# yabr6v3.net
KiCad netlist of a schematic drawn in EAGLE
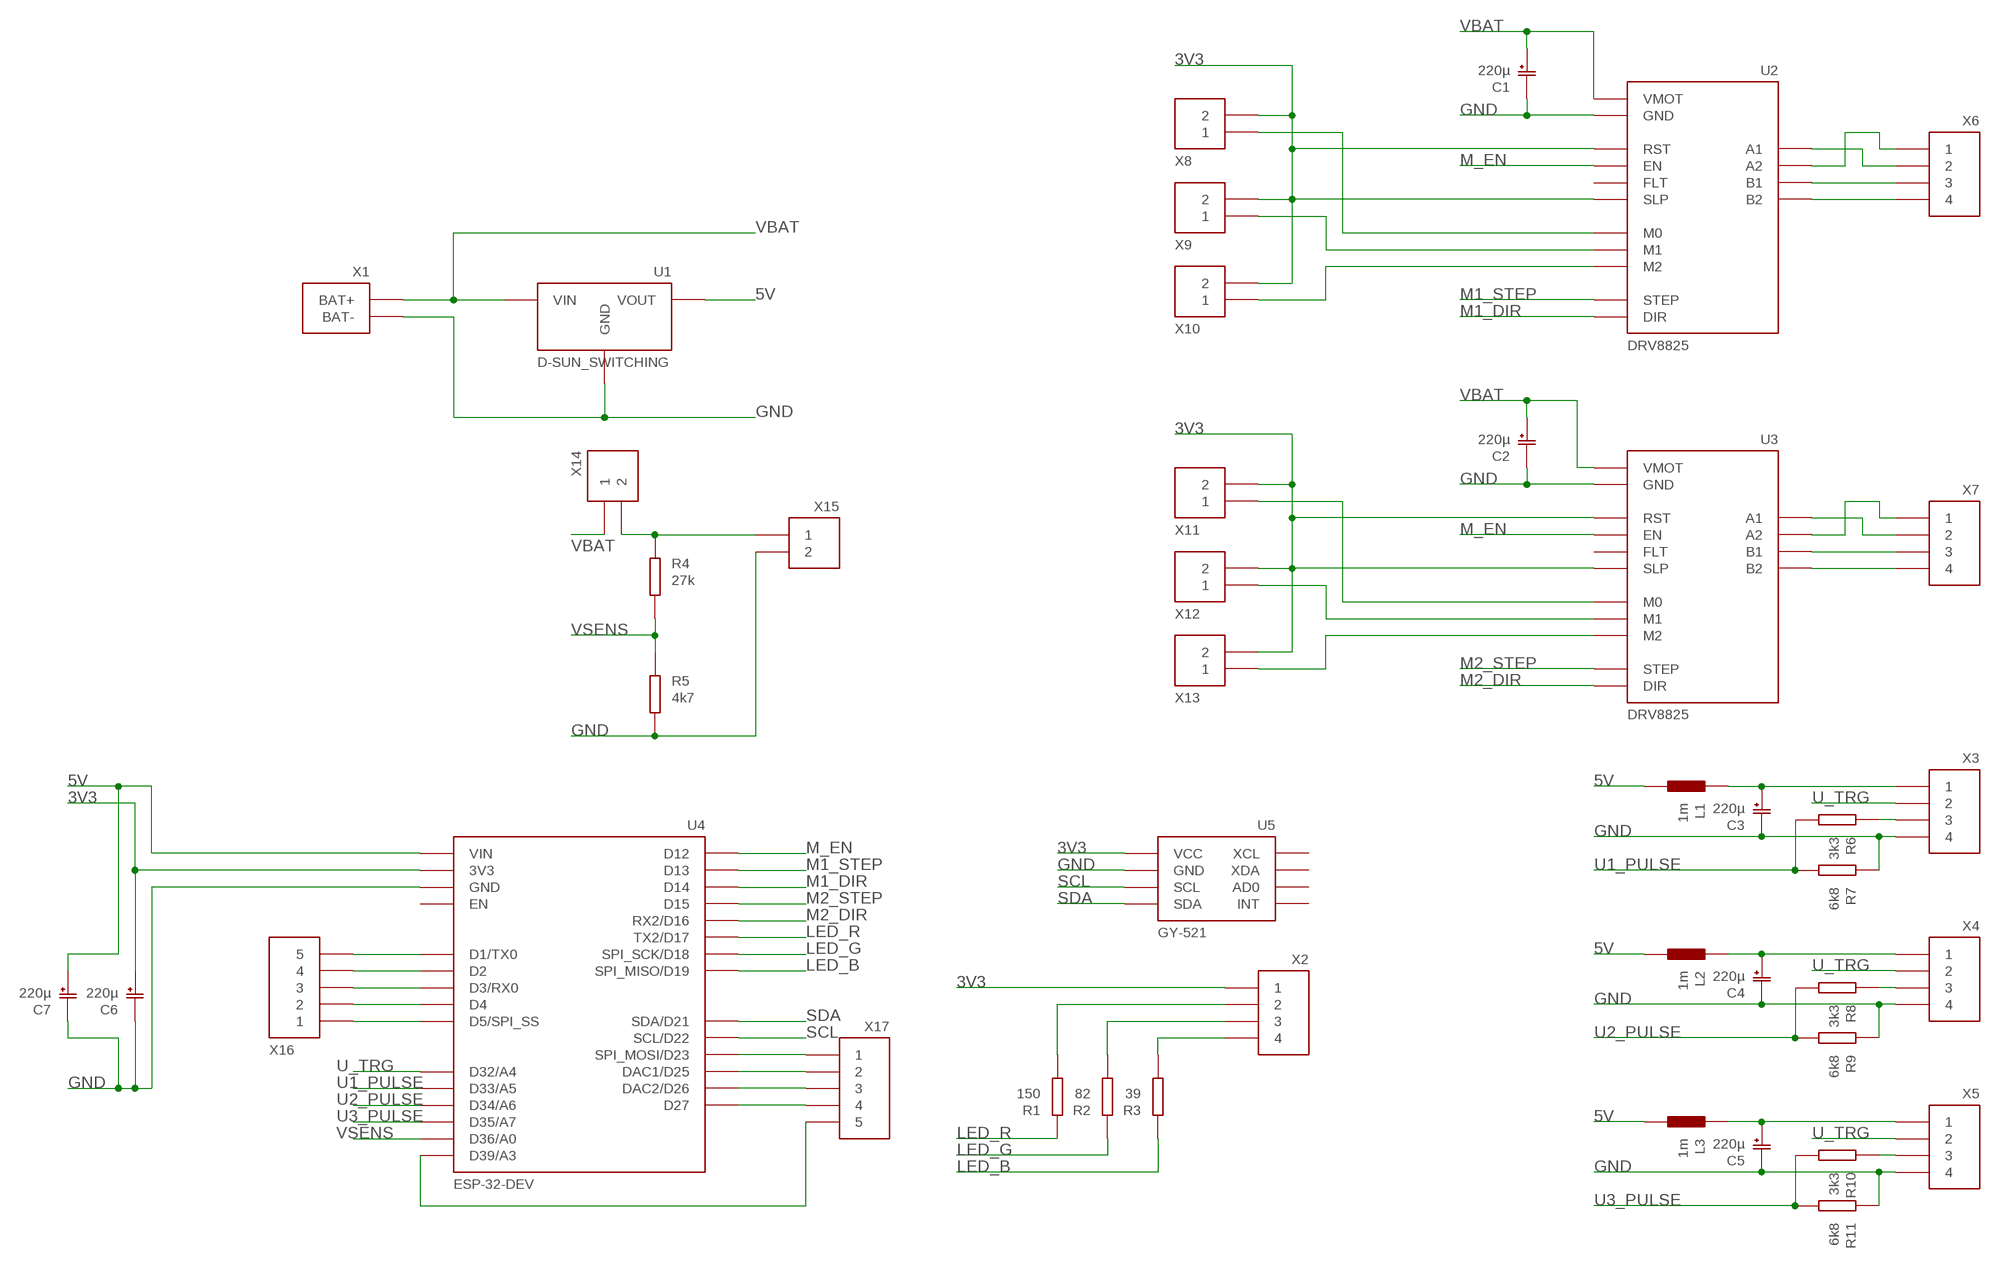
[diagram p0: schematic, sheet 1]

(export (version "E")
  (design (tool "Eeschema 10.0.6"))
  (components
    (comp (ref "C1")
      (value "220µ")
      (footprint "eagle-import:CPOL_3,5")
      (libsource (lib "eagle-import") (part "CPOL3,5"))
    )
    (comp (ref "C2")
      (value "220µ")
      (footprint "eagle-import:CPOL_3,5")
      (libsource (lib "eagle-import") (part "CPOL3,5"))
    )
    (comp (ref "C3")
      (value "220µ")
      (footprint "eagle-import:CPOL_3,5")
      (libsource (lib "eagle-import") (part "CPOL3,5"))
    )
    (comp (ref "C4")
      (value "220µ")
      (footprint "eagle-import:CPOL_3,5")
      (libsource (lib "eagle-import") (part "CPOL3,5"))
    )
    (comp (ref "C5")
      (value "220µ")
      (footprint "eagle-import:CPOL_3,5")
      (libsource (lib "eagle-import") (part "CPOL3,5"))
    )
    (comp (ref "C6")
      (value "220µ")
      (footprint "eagle-import:CPOL_3,5")
      (libsource (lib "eagle-import") (part "CPOL3,5"))
    )
    (comp (ref "C7")
      (value "220µ")
      (footprint "eagle-import:CPOL_3,5")
      (libsource (lib "eagle-import") (part "CPOL3,5"))
    )
    (comp (ref "L1")
      (value "1m")
      (footprint "eagle-import:NEOSID_SD75")
      (libsource (lib "eagle-import") (part "L_NEO"))
    )
    (comp (ref "L2")
      (value "1m")
      (footprint "eagle-import:NEOSID_SD75")
      (libsource (lib "eagle-import") (part "L_NEO"))
    )
    (comp (ref "L3")
      (value "1m")
      (footprint "eagle-import:NEOSID_SD75")
      (libsource (lib "eagle-import") (part "L_NEO"))
    )
    (comp (ref "R1")
      (value "150")
      (footprint "eagle-import:R_12")
      (libsource (lib "eagle-import") (part "R12"))
    )
    (comp (ref "R2")
      (value "82")
      (footprint "eagle-import:R_12")
      (libsource (lib "eagle-import") (part "R12"))
    )
    (comp (ref "R3")
      (value "39")
      (footprint "eagle-import:R_12")
      (libsource (lib "eagle-import") (part "R12"))
    )
    (comp (ref "R4")
      (value "27k")
      (footprint "eagle-import:R_12")
      (libsource (lib "eagle-import") (part "R12"))
    )
    (comp (ref "R5")
      (value "4k7")
      (footprint "eagle-import:R_12")
      (libsource (lib "eagle-import") (part "R12"))
    )
    (comp (ref "R6")
      (value "3k3")
      (footprint "eagle-import:R_12")
      (libsource (lib "eagle-import") (part "R12"))
    )
    (comp (ref "R7")
      (value "6k8")
      (footprint "eagle-import:R_12")
      (libsource (lib "eagle-import") (part "R12"))
    )
    (comp (ref "R8")
      (value "3k3")
      (footprint "eagle-import:R_12")
      (libsource (lib "eagle-import") (part "R12"))
    )
    (comp (ref "R9")
      (value "6k8")
      (footprint "eagle-import:R_12")
      (libsource (lib "eagle-import") (part "R12"))
    )
    (comp (ref "R10")
      (value "3k3")
      (footprint "eagle-import:R_12")
      (libsource (lib "eagle-import") (part "R12"))
    )
    (comp (ref "R11")
      (value "6k8")
      (footprint "eagle-import:R_12")
      (libsource (lib "eagle-import") (part "R12"))
    )
    (comp (ref "U1")
      (value "D-SUN_SWITCHING")
      (footprint "eagle-import:D-SUN_SWITCHING")
      (libsource (lib "eagle-import") (part "D-SUN_SWITCHING"))
    )
    (comp (ref "U2")
      (value "DRV8825")
      (footprint "eagle-import:DRV8825")
      (libsource (lib "eagle-import") (part "DRV8825"))
    )
    (comp (ref "U3")
      (value "DRV8825")
      (footprint "eagle-import:DRV8825")
      (libsource (lib "eagle-import") (part "DRV8825"))
    )
    (comp (ref "U4")
      (value "ESP-32-DEV")
      (footprint "eagle-import:ESP-32-DEV")
      (libsource (lib "eagle-import") (part "ESP-32-DEV"))
    )
    (comp (ref "U5")
      (value "GY-521")
      (footprint "eagle-import:GY-521")
      (libsource (lib "eagle-import") (part "GY-521"))
    )
    (comp (ref "X1")
      (value "BAT")
      (footprint "eagle-import:BAT")
      (libsource (lib "eagle-import") (part "BAT"))
    )
    (comp (ref "X2") (value "X4") (footprint "eagle-import:X4") (libsource (lib "eagle-import") (part "X4")))
    (comp (ref "X3") (value "X4") (footprint "eagle-import:X4") (libsource (lib "eagle-import") (part "X4")))
    (comp (ref "X4") (value "X4") (footprint "eagle-import:X4") (libsource (lib "eagle-import") (part "X4")))
    (comp (ref "X5") (value "X4") (footprint "eagle-import:X4") (libsource (lib "eagle-import") (part "X4")))
    (comp (ref "X6") (value "X4") (footprint "eagle-import:X4") (libsource (lib "eagle-import") (part "X4")))
    (comp (ref "X7") (value "X4") (footprint "eagle-import:X4") (libsource (lib "eagle-import") (part "X4")))
    (comp (ref "X8") (value "X2") (footprint "eagle-import:X2") (libsource (lib "eagle-import") (part "X2")))
    (comp (ref "X9") (value "X2") (footprint "eagle-import:X2") (libsource (lib "eagle-import") (part "X2")))
    (comp (ref "X10") (value "X2") (footprint "eagle-import:X2") (libsource (lib "eagle-import") (part "X2")))
    (comp (ref "X11") (value "X2") (footprint "eagle-import:X2") (libsource (lib "eagle-import") (part "X2")))
    (comp (ref "X12") (value "X2") (footprint "eagle-import:X2") (libsource (lib "eagle-import") (part "X2")))
    (comp (ref "X13") (value "X2") (footprint "eagle-import:X2") (libsource (lib "eagle-import") (part "X2")))
    (comp (ref "X14") (value "X2") (footprint "eagle-import:X2") (libsource (lib "eagle-import") (part "X2")))
    (comp (ref "X15") (value "X2") (footprint "eagle-import:X2") (libsource (lib "eagle-import") (part "X2")))
    (comp (ref "X16") (value "X5") (footprint "eagle-import:X5") (libsource (lib "eagle-import") (part "X5")))
    (comp (ref "X17") (value "X5") (footprint "eagle-import:X5") (libsource (lib "eagle-import") (part "X5")))
  )
  (nets
    (net (code "1") (name "/3V3") (class "Default")
      (node (ref "C6") (pin "P") (pinfunction "+_P") (pintype "bidirectional"))
      (node (ref "U2") (pin "P$11") (pinfunction "SLP_P$11") (pintype "bidirectional"))
      (node (ref "U2") (pin "P$12") (pinfunction "RST_P$12") (pintype "bidirectional"))
      (node (ref "U3") (pin "P$11") (pinfunction "SLP_P$11") (pintype "bidirectional"))
      (node (ref "U3") (pin "P$12") (pinfunction "RST_P$12") (pintype "bidirectional"))
      (node (ref "U4") (pin "P$15") (pinfunction "3V3_P$15") (pintype "bidirectional"))
      (node (ref "U5") (pin "P$8") (pinfunction "VCC_P$8") (pintype "bidirectional"))
      (node (ref "X10") (pin "P$2") (pinfunction "2_P$2") (pintype "bidirectional"))
      (node (ref "X11") (pin "P$2") (pinfunction "2_P$2") (pintype "bidirectional"))
      (node (ref "X12") (pin "P$2") (pinfunction "2_P$2") (pintype "bidirectional"))
      (node (ref "X13") (pin "P$2") (pinfunction "2_P$2") (pintype "bidirectional"))
      (node (ref "X2") (pin "P$1") (pinfunction "1_P$1") (pintype "bidirectional"))
      (node (ref "X8") (pin "P$2") (pinfunction "2_P$2") (pintype "bidirectional"))
      (node (ref "X9") (pin "P$2") (pinfunction "2_P$2") (pintype "bidirectional"))
    )
    (net (code "2") (name "/5V") (class "Default")
      (node (ref "C7") (pin "P") (pinfunction "+_P") (pintype "bidirectional"))
      (node (ref "L1") (pin "P") (pinfunction "P$2_P") (pintype "bidirectional"))
      (node (ref "L2") (pin "P") (pinfunction "P$2_P") (pintype "bidirectional"))
      (node (ref "L3") (pin "P") (pinfunction "P$2_P") (pintype "bidirectional"))
      (node (ref "U1") (pin "PO") (pinfunction "VOUT_PO") (pintype "bidirectional"))
      (node (ref "U1") (pin "PO2") (pinfunction "VOUT_PO2") (pintype "bidirectional"))
      (node (ref "U4") (pin "P$16") (pinfunction "VIN_P$16") (pintype "bidirectional"))
    )
    (net (code "3") (name "/GND") (class "Default")
      (node (ref "C1") (pin "N") (pinfunction "-_N") (pintype "bidirectional"))
      (node (ref "C2") (pin "N") (pinfunction "-_N") (pintype "bidirectional"))
      (node (ref "C3") (pin "N") (pinfunction "-_N") (pintype "bidirectional"))
      (node (ref "C4") (pin "N") (pinfunction "-_N") (pintype "bidirectional"))
      (node (ref "C5") (pin "N") (pinfunction "-_N") (pintype "bidirectional"))
      (node (ref "C6") (pin "N") (pinfunction "-_N") (pintype "bidirectional"))
      (node (ref "C7") (pin "N") (pinfunction "-_N") (pintype "bidirectional"))
      (node (ref "R11") (pin "N") (pinfunction "P$1_N") (pintype "bidirectional"))
      (node (ref "R5") (pin "P") (pinfunction "P$2_P") (pintype "bidirectional"))
      (node (ref "R7") (pin "N") (pinfunction "P$1_N") (pintype "bidirectional"))
      (node (ref "R9") (pin "N") (pinfunction "P$1_N") (pintype "bidirectional"))
      (node (ref "U1") (pin "NI") (pinfunction "GND_NI") (pintype "bidirectional"))
      (node (ref "U1") (pin "NI2") (pinfunction "GND_NI2") (pintype "bidirectional"))
      (node (ref "U1") (pin "NO") (pinfunction "GND_NO") (pintype "bidirectional"))
      (node (ref "U1") (pin "NO2") (pinfunction "GND_NO2") (pintype "bidirectional"))
      (node (ref "U2") (pin "P$2") (pinfunction "GND_P$2") (pintype "bidirectional"))
      (node (ref "U2") (pin "P$8") (pinfunction "GND_P$8") (pintype "bidirectional"))
      (node (ref "U3") (pin "P$2") (pinfunction "GND_P$2") (pintype "bidirectional"))
      (node (ref "U3") (pin "P$8") (pinfunction "GND_P$8") (pintype "bidirectional"))
      (node (ref "U4") (pin "P$14") (pinfunction "GND_P$14") (pintype "bidirectional"))
      (node (ref "U4") (pin "P$17") (pinfunction "GND_P$17") (pintype "bidirectional"))
      (node (ref "U5") (pin "P$7") (pinfunction "GND_P$7") (pintype "bidirectional"))
      (node (ref "X1") (pin "N") (pinfunction "BAT-_N") (pintype "bidirectional"))
      (node (ref "X15") (pin "P$2") (pinfunction "2_P$2") (pintype "bidirectional"))
      (node (ref "X3") (pin "P$4") (pinfunction "4_P$4") (pintype "bidirectional"))
      (node (ref "X4") (pin "P$4") (pinfunction "4_P$4") (pintype "bidirectional"))
      (node (ref "X5") (pin "P$4") (pinfunction "4_P$4") (pintype "bidirectional"))
    )
    (net (code "4") (name "/LED_B") (class "Default")
      (node (ref "R3") (pin "N") (pinfunction "P$1_N") (pintype "bidirectional"))
      (node (ref "U4") (pin "P$6") (pinfunction "SPI_MISO/D19_P$6") (pintype "bidirectional"))
    )
    (net (code "5") (name "/LED_G") (class "Default")
      (node (ref "R2") (pin "N") (pinfunction "P$1_N") (pintype "bidirectional"))
      (node (ref "U4") (pin "P$7") (pinfunction "SPI_SCK/D18_P$7") (pintype "bidirectional"))
    )
    (net (code "6") (name "/LED_R") (class "Default")
      (node (ref "R1") (pin "N") (pinfunction "P$1_N") (pintype "bidirectional"))
      (node (ref "U4") (pin "P$9") (pinfunction "TX2/D17_P$9") (pintype "bidirectional"))
    )
    (net (code "7") (name "/M1_DIR") (class "Default")
      (node (ref "U2") (pin "P$9") (pinfunction "DIR_P$9") (pintype "bidirectional"))
      (node (ref "U4") (pin "P$20") (pinfunction "D14_P$20") (pintype "bidirectional"))
    )
    (net (code "8") (name "/M1_STEP") (class "Default")
      (node (ref "U2") (pin "P$10") (pinfunction "STEP_P$10") (pintype "bidirectional"))
      (node (ref "U4") (pin "P$18") (pinfunction "D13_P$18") (pintype "bidirectional"))
    )
    (net (code "9") (name "/M2_DIR") (class "Default")
      (node (ref "U3") (pin "P$9") (pinfunction "DIR_P$9") (pintype "bidirectional"))
      (node (ref "U4") (pin "P$10") (pinfunction "RX2/D16_P$10") (pintype "bidirectional"))
    )
    (net (code "10") (name "/M2_STEP") (class "Default")
      (node (ref "U3") (pin "P$10") (pinfunction "STEP_P$10") (pintype "bidirectional"))
      (node (ref "U4") (pin "P$13") (pinfunction "D15_P$13") (pintype "bidirectional"))
    )
    (net (code "11") (name "/M_EN") (class "Default")
      (node (ref "U2") (pin "P$16") (pinfunction "EN_P$16") (pintype "bidirectional"))
      (node (ref "U3") (pin "P$16") (pinfunction "EN_P$16") (pintype "bidirectional"))
      (node (ref "U4") (pin "P$19") (pinfunction "D12_P$19") (pintype "bidirectional"))
    )
    (net (code "12") (name "/SCL") (class "Default")
      (node (ref "U4") (pin "P$2") (pinfunction "SCL/D22_P$2") (pintype "bidirectional"))
      (node (ref "U5") (pin "P$6") (pinfunction "SCL_P$6") (pintype "bidirectional"))
    )
    (net (code "13") (name "/SDA") (class "Default")
      (node (ref "U4") (pin "P$5") (pinfunction "SDA/D21_P$5") (pintype "bidirectional"))
      (node (ref "U5") (pin "P$5") (pinfunction "SDA_P$5") (pintype "bidirectional"))
    )
    (net (code "14") (name "/U1_PULSE") (class "Default")
      (node (ref "R6") (pin "P") (pinfunction "P$2_P") (pintype "bidirectional"))
      (node (ref "R7") (pin "P") (pinfunction "P$2_P") (pintype "bidirectional"))
      (node (ref "U4") (pin "P$24") (pinfunction "D33/A5_P$24") (pintype "bidirectional"))
    )
    (net (code "15") (name "/U2_PULSE") (class "Default")
      (node (ref "R8") (pin "P") (pinfunction "P$2_P") (pintype "bidirectional"))
      (node (ref "R9") (pin "P") (pinfunction "P$2_P") (pintype "bidirectional"))
      (node (ref "U4") (pin "P$27") (pinfunction "D34/A6_P$27") (pintype "bidirectional"))
    )
    (net (code "16") (name "/U3_PULSE") (class "Default")
      (node (ref "R10") (pin "P") (pinfunction "P$2_P") (pintype "bidirectional"))
      (node (ref "R11") (pin "P") (pinfunction "P$2_P") (pintype "bidirectional"))
      (node (ref "U4") (pin "P$26") (pinfunction "D35/A7_P$26") (pintype "bidirectional"))
    )
    (net (code "17") (name "/U_TRG") (class "Default")
      (node (ref "U4") (pin "P$25") (pinfunction "D32/A4_P$25") (pintype "bidirectional"))
      (node (ref "X3") (pin "P$2") (pinfunction "2_P$2") (pintype "bidirectional"))
      (node (ref "X4") (pin "P$2") (pinfunction "2_P$2") (pintype "bidirectional"))
      (node (ref "X5") (pin "P$2") (pinfunction "2_P$2") (pintype "bidirectional"))
    )
    (net (code "18") (name "/VBAT") (class "Default")
      (node (ref "C1") (pin "P") (pinfunction "+_P") (pintype "bidirectional"))
      (node (ref "C2") (pin "P") (pinfunction "+_P") (pintype "bidirectional"))
      (node (ref "U1") (pin "PI") (pinfunction "VIN_PI") (pintype "bidirectional"))
      (node (ref "U1") (pin "PI2") (pinfunction "VIN_PI2") (pintype "bidirectional"))
      (node (ref "U2") (pin "P$1") (pinfunction "VMOT_P$1") (pintype "bidirectional"))
      (node (ref "U3") (pin "P$1") (pinfunction "VMOT_P$1") (pintype "bidirectional"))
      (node (ref "X1") (pin "P") (pinfunction "BAT+_P") (pintype "bidirectional"))
      (node (ref "X14") (pin "P$1") (pinfunction "1_P$1") (pintype "bidirectional"))
    )
    (net (code "19") (name "/VSENS") (class "Default")
      (node (ref "R4") (pin "P") (pinfunction "P$2_P") (pintype "bidirectional"))
      (node (ref "R5") (pin "N") (pinfunction "P$1_N") (pintype "bidirectional"))
      (node (ref "U4") (pin "P$29") (pinfunction "D36/A0_P$29") (pintype "bidirectional"))
    )
    (net (code "20") (name "Net-(C3-+)") (class "Default")
      (node (ref "C3") (pin "P") (pinfunction "+_P") (pintype "bidirectional"))
      (node (ref "L1") (pin "N") (pinfunction "P$1_N") (pintype "bidirectional"))
      (node (ref "X3") (pin "P$1") (pinfunction "1_P$1") (pintype "bidirectional"))
    )
    (net (code "21") (name "Net-(C4-+)") (class "Default")
      (node (ref "C4") (pin "P") (pinfunction "+_P") (pintype "bidirectional"))
      (node (ref "L2") (pin "N") (pinfunction "P$1_N") (pintype "bidirectional"))
      (node (ref "X4") (pin "P$1") (pinfunction "1_P$1") (pintype "bidirectional"))
    )
    (net (code "22") (name "Net-(C5-+)") (class "Default")
      (node (ref "C5") (pin "P") (pinfunction "+_P") (pintype "bidirectional"))
      (node (ref "L3") (pin "N") (pinfunction "P$1_N") (pintype "bidirectional"))
      (node (ref "X5") (pin "P$1") (pinfunction "1_P$1") (pintype "bidirectional"))
    )
    (net (code "23") (name "Net-(R1-P$2)") (class "Default")
      (node (ref "R1") (pin "P") (pinfunction "P$2_P") (pintype "bidirectional"))
      (node (ref "X2") (pin "P$2") (pinfunction "2_P$2") (pintype "bidirectional"))
    )
    (net (code "24") (name "Net-(R2-P$2)") (class "Default")
      (node (ref "R2") (pin "P") (pinfunction "P$2_P") (pintype "bidirectional"))
      (node (ref "X2") (pin "P$3") (pinfunction "3_P$3") (pintype "bidirectional"))
    )
    (net (code "25") (name "Net-(R3-P$2)") (class "Default")
      (node (ref "R3") (pin "P") (pinfunction "P$2_P") (pintype "bidirectional"))
      (node (ref "X2") (pin "P$4") (pinfunction "4_P$4") (pintype "bidirectional"))
    )
    (net (code "26") (name "Net-(R4-P$1)") (class "Default")
      (node (ref "R4") (pin "N") (pinfunction "P$1_N") (pintype "bidirectional"))
      (node (ref "X14") (pin "P$2") (pinfunction "2_P$2") (pintype "bidirectional"))
      (node (ref "X15") (pin "P$1") (pinfunction "1_P$1") (pintype "bidirectional"))
    )
    (net (code "27") (name "Net-(R6-P$1)") (class "Default")
      (node (ref "R6") (pin "N") (pinfunction "P$1_N") (pintype "bidirectional"))
      (node (ref "X3") (pin "P$3") (pinfunction "3_P$3") (pintype "bidirectional"))
    )
    (net (code "28") (name "Net-(R8-P$1)") (class "Default")
      (node (ref "R8") (pin "N") (pinfunction "P$1_N") (pintype "bidirectional"))
      (node (ref "X4") (pin "P$3") (pinfunction "3_P$3") (pintype "bidirectional"))
    )
    (net (code "29") (name "Net-(R10-P$1)") (class "Default")
      (node (ref "R10") (pin "N") (pinfunction "P$1_N") (pintype "bidirectional"))
      (node (ref "X5") (pin "P$3") (pinfunction "3_P$3") (pintype "bidirectional"))
    )
    (net (code "30") (name "Net-(U2-A1)") (class "Default")
      (node (ref "U2") (pin "P$5") (pinfunction "A1_P$5") (pintype "bidirectional"))
      (node (ref "X6") (pin "P$2") (pinfunction "2_P$2") (pintype "bidirectional"))
    )
    (net (code "31") (name "Net-(U2-A2)") (class "Default")
      (node (ref "U2") (pin "P$6") (pinfunction "A2_P$6") (pintype "bidirectional"))
      (node (ref "X6") (pin "P$1") (pinfunction "1_P$1") (pintype "bidirectional"))
    )
    (net (code "32") (name "Net-(U2-B1)") (class "Default")
      (node (ref "U2") (pin "P$4") (pinfunction "B1_P$4") (pintype "bidirectional"))
      (node (ref "X6") (pin "P$3") (pinfunction "3_P$3") (pintype "bidirectional"))
    )
    (net (code "33") (name "Net-(U2-B2)") (class "Default")
      (node (ref "U2") (pin "P$3") (pinfunction "B2_P$3") (pintype "bidirectional"))
      (node (ref "X6") (pin "P$4") (pinfunction "4_P$4") (pintype "bidirectional"))
    )
    (net (code "34") (name "Net-(U2-M0)") (class "Default")
      (node (ref "U2") (pin "P$15") (pinfunction "M0_P$15") (pintype "bidirectional"))
      (node (ref "X8") (pin "P$1") (pinfunction "1_P$1") (pintype "bidirectional"))
    )
    (net (code "35") (name "Net-(U2-M1)") (class "Default")
      (node (ref "U2") (pin "P$14") (pinfunction "M1_P$14") (pintype "bidirectional"))
      (node (ref "X9") (pin "P$1") (pinfunction "1_P$1") (pintype "bidirectional"))
    )
    (net (code "36") (name "Net-(U2-M2)") (class "Default")
      (node (ref "U2") (pin "P$13") (pinfunction "M2_P$13") (pintype "bidirectional"))
      (node (ref "X10") (pin "P$1") (pinfunction "1_P$1") (pintype "bidirectional"))
    )
    (net (code "37") (name "Net-(U3-A1)") (class "Default")
      (node (ref "U3") (pin "P$5") (pinfunction "A1_P$5") (pintype "bidirectional"))
      (node (ref "X7") (pin "P$2") (pinfunction "2_P$2") (pintype "bidirectional"))
    )
    (net (code "38") (name "Net-(U3-A2)") (class "Default")
      (node (ref "U3") (pin "P$6") (pinfunction "A2_P$6") (pintype "bidirectional"))
      (node (ref "X7") (pin "P$1") (pinfunction "1_P$1") (pintype "bidirectional"))
    )
    (net (code "39") (name "Net-(U3-B1)") (class "Default")
      (node (ref "U3") (pin "P$4") (pinfunction "B1_P$4") (pintype "bidirectional"))
      (node (ref "X7") (pin "P$3") (pinfunction "3_P$3") (pintype "bidirectional"))
    )
    (net (code "40") (name "Net-(U3-B2)") (class "Default")
      (node (ref "U3") (pin "P$3") (pinfunction "B2_P$3") (pintype "bidirectional"))
      (node (ref "X7") (pin "P$4") (pinfunction "4_P$4") (pintype "bidirectional"))
    )
    (net (code "41") (name "Net-(U3-M0)") (class "Default")
      (node (ref "U3") (pin "P$15") (pinfunction "M0_P$15") (pintype "bidirectional"))
      (node (ref "X11") (pin "P$1") (pinfunction "1_P$1") (pintype "bidirectional"))
    )
    (net (code "42") (name "Net-(U3-M1)") (class "Default")
      (node (ref "U3") (pin "P$14") (pinfunction "M1_P$14") (pintype "bidirectional"))
      (node (ref "X12") (pin "P$1") (pinfunction "1_P$1") (pintype "bidirectional"))
    )
    (net (code "43") (name "Net-(U3-M2)") (class "Default")
      (node (ref "U3") (pin "P$13") (pinfunction "M2_P$13") (pintype "bidirectional"))
      (node (ref "X13") (pin "P$1") (pinfunction "1_P$1") (pintype "bidirectional"))
    )
    (net (code "44") (name "Net-(U4-D1{slash}TX0)") (class "Default")
      (node (ref "U4") (pin "P$3") (pinfunction "D1/TX0_P$3") (pintype "bidirectional"))
      (node (ref "X16") (pin "P$5") (pinfunction "5_P$5") (pintype "bidirectional"))
    )
    (net (code "45") (name "Net-(U4-D2)") (class "Default")
      (node (ref "U4") (pin "P$12") (pinfunction "D2_P$12") (pintype "bidirectional"))
      (node (ref "X16") (pin "P$4") (pinfunction "4_P$4") (pintype "bidirectional"))
    )
    (net (code "46") (name "Net-(U4-D3{slash}RX0)") (class "Default")
      (node (ref "U4") (pin "P$4") (pinfunction "D3/RX0_P$4") (pintype "bidirectional"))
      (node (ref "X16") (pin "P$3") (pinfunction "3_P$3") (pintype "bidirectional"))
    )
    (net (code "47") (name "Net-(U4-D4)") (class "Default")
      (node (ref "U4") (pin "P$11") (pinfunction "D4_P$11") (pintype "bidirectional"))
      (node (ref "X16") (pin "P$2") (pinfunction "2_P$2") (pintype "bidirectional"))
    )
    (net (code "48") (name "Net-(U4-D5{slash}SPI_SS)") (class "Default")
      (node (ref "U4") (pin "P$8") (pinfunction "D5/SPI_SS_P$8") (pintype "bidirectional"))
      (node (ref "X16") (pin "P$1") (pinfunction "1_P$1") (pintype "bidirectional"))
    )
    (net (code "49") (name "Net-(U4-D27)") (class "Default")
      (node (ref "U4") (pin "P$21") (pinfunction "D27_P$21") (pintype "bidirectional"))
      (node (ref "X17") (pin "P$4") (pinfunction "4_P$4") (pintype "bidirectional"))
    )
    (net (code "50") (name "Net-(U4-D39{slash}A3)") (class "Default")
      (node (ref "U4") (pin "P$28") (pinfunction "D39/A3_P$28") (pintype "bidirectional"))
      (node (ref "X17") (pin "P$5") (pinfunction "5_P$5") (pintype "bidirectional"))
    )
    (net (code "51") (name "Net-(U4-DAC1{slash}D25)") (class "Default")
      (node (ref "U4") (pin "P$23") (pinfunction "DAC1/D25_P$23") (pintype "bidirectional"))
      (node (ref "X17") (pin "P$2") (pinfunction "2_P$2") (pintype "bidirectional"))
    )
    (net (code "52") (name "Net-(U4-DAC2{slash}D26)") (class "Default")
      (node (ref "U4") (pin "P$22") (pinfunction "DAC2/D26_P$22") (pintype "bidirectional"))
      (node (ref "X17") (pin "P$3") (pinfunction "3_P$3") (pintype "bidirectional"))
    )
    (net (code "53") (name "Net-(U4-SPI_MOSI{slash}D23)") (class "Default")
      (node (ref "U4") (pin "P$1") (pinfunction "SPI_MOSI/D23_P$1") (pintype "bidirectional"))
      (node (ref "X17") (pin "P$1") (pinfunction "1_P$1") (pintype "bidirectional"))
    )
    (net (code "54") (name "unconnected-(U2-FLT-PadP$7)") (class "Default")
      (node (ref "U2") (pin "P$7") (pinfunction "FLT_P$7") (pintype "bidirectional"))
    )
    (net (code "55") (name "unconnected-(U3-FLT-PadP$7)") (class "Default")
      (node (ref "U3") (pin "P$7") (pinfunction "FLT_P$7") (pintype "bidirectional"))
    )
    (net (code "56") (name "unconnected-(U4-EN-PadP$30)") (class "Default")
      (node (ref "U4") (pin "P$30") (pinfunction "EN_P$30") (pintype "bidirectional"))
    )
    (net (code "57") (name "unconnected-(U5-AD0-PadP$2)") (class "Default")
      (node (ref "U5") (pin "P$2") (pinfunction "AD0_P$2") (pintype "bidirectional"))
    )
    (net (code "58") (name "unconnected-(U5-INT-PadP$1)") (class "Default")
      (node (ref "U5") (pin "P$1") (pinfunction "INT_P$1") (pintype "bidirectional"))
    )
    (net (code "59") (name "unconnected-(U5-XCL-PadP$4)") (class "Default")
      (node (ref "U5") (pin "P$4") (pinfunction "XCL_P$4") (pintype "bidirectional"))
    )
    (net (code "60") (name "unconnected-(U5-XDA-PadP$3)") (class "Default")
      (node (ref "U5") (pin "P$3") (pinfunction "XDA_P$3") (pintype "bidirectional"))
    )
  )
)
